# lucky7.net
KiCad netlist of a schematic drawn in EAGLE
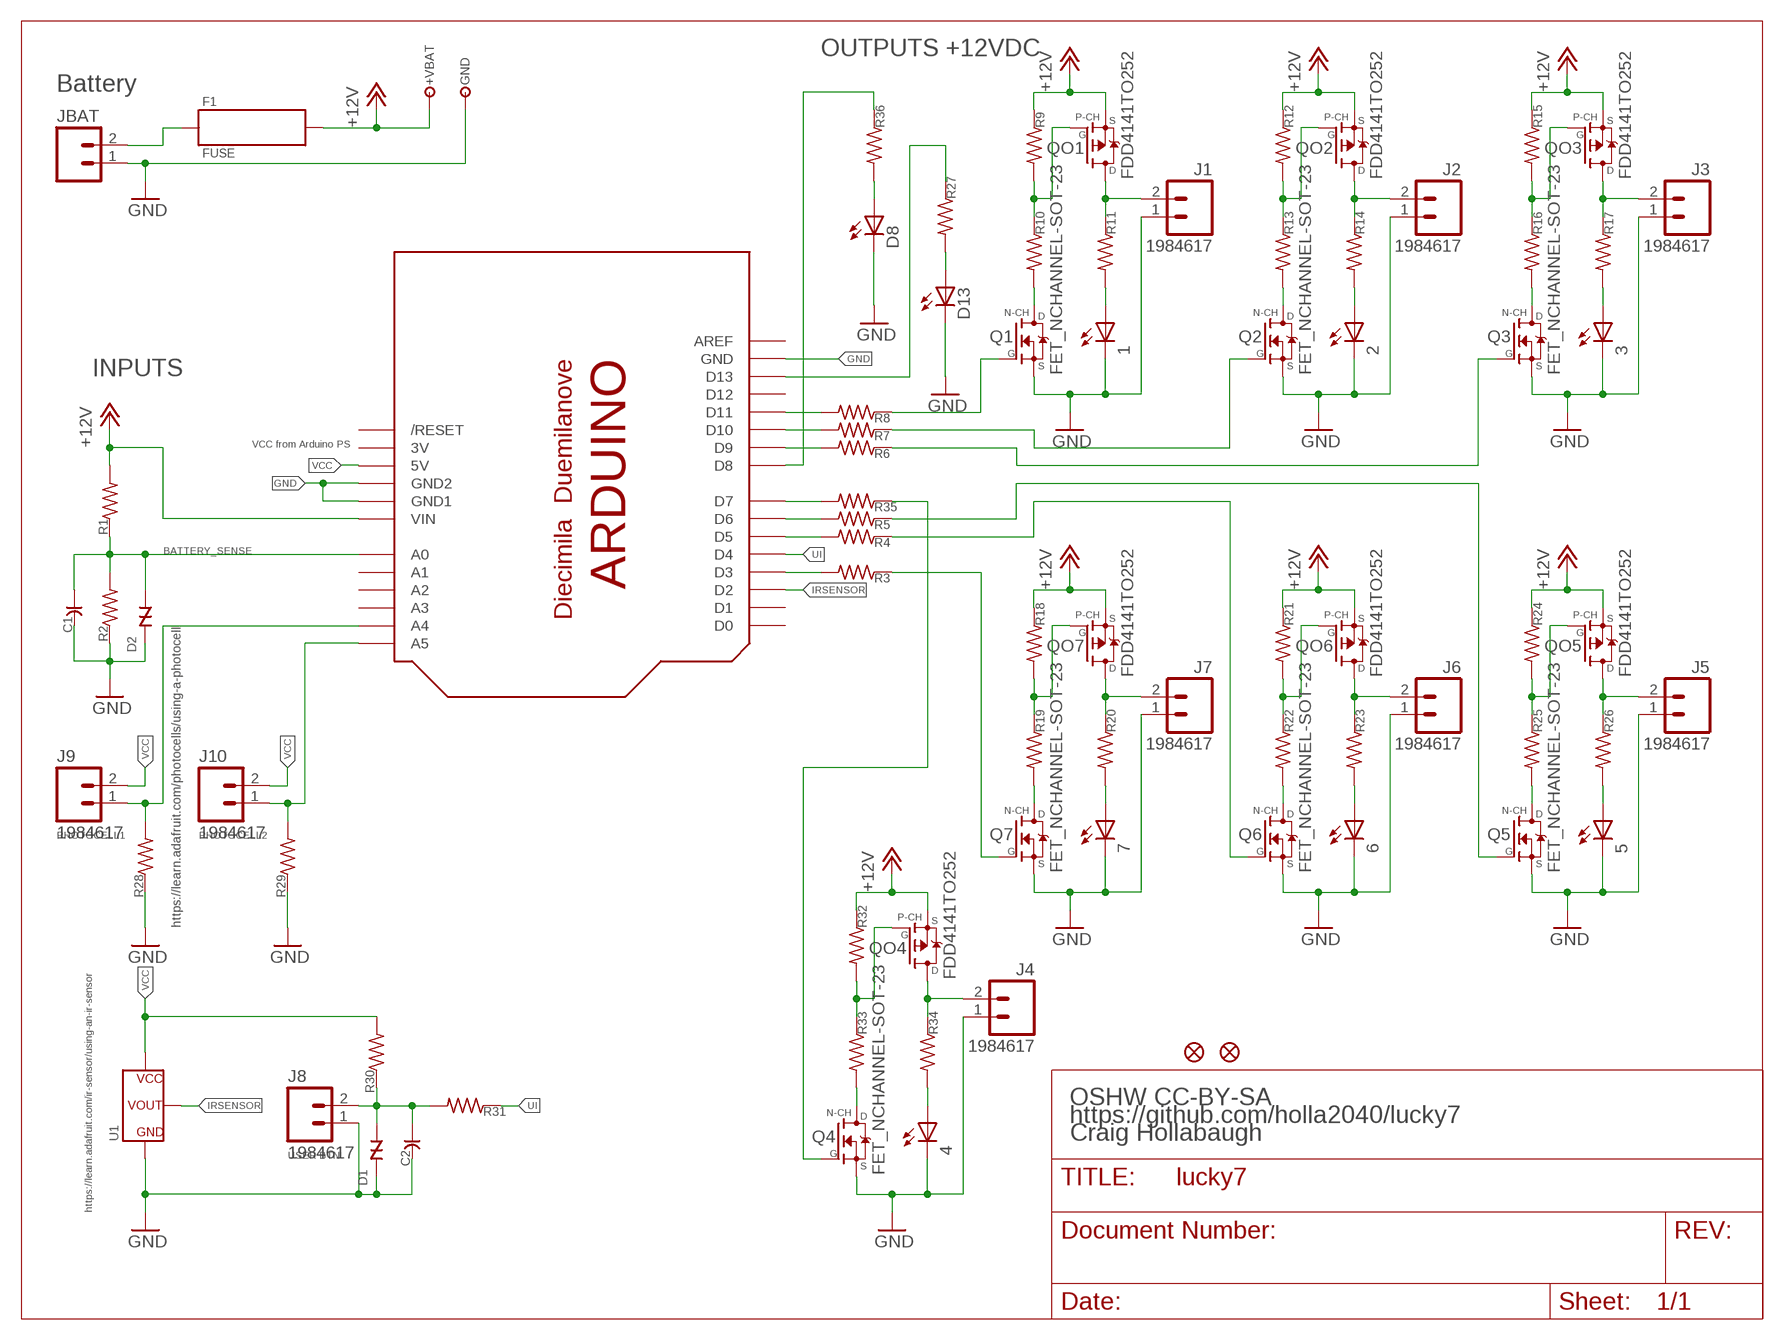
[diagram p0: schematic, sheet 1]

(export (version "E")
  (design (tool "Eeschema 10.0.6"))
  (components
    (comp (ref "+VBAT")
      (value "TESTPOINTTHRU")
      (footprint "eagle-import:TPTHRU")
      (libsource (lib "eagle-import") (part "TESTPOINTTHRU"))
    )
    (comp (ref "1")
      (value "LEDCHIP-LED0805")
      (footprint "eagle-import:CHIP-LED0805")
      (libsource (lib "eagle-import") (part "LEDCHIP-LED0805"))
    )
    (comp (ref "2")
      (value "LEDCHIP-LED0805")
      (footprint "eagle-import:CHIP-LED0805")
      (libsource (lib "eagle-import") (part "LEDCHIP-LED0805"))
    )
    (comp (ref "3")
      (value "LEDCHIP-LED0805")
      (footprint "eagle-import:CHIP-LED0805")
      (libsource (lib "eagle-import") (part "LEDCHIP-LED0805"))
    )
    (comp (ref "4")
      (value "LEDCHIP-LED0805")
      (footprint "eagle-import:CHIP-LED0805")
      (libsource (lib "eagle-import") (part "LEDCHIP-LED0805"))
    )
    (comp (ref "5")
      (value "LEDCHIP-LED0805")
      (footprint "eagle-import:CHIP-LED0805")
      (libsource (lib "eagle-import") (part "LEDCHIP-LED0805"))
    )
    (comp (ref "6")
      (value "LEDCHIP-LED0805")
      (footprint "eagle-import:CHIP-LED0805")
      (libsource (lib "eagle-import") (part "LEDCHIP-LED0805"))
    )
    (comp (ref "7")
      (value "LEDCHIP-LED0805")
      (footprint "eagle-import:CHIP-LED0805")
      (libsource (lib "eagle-import") (part "LEDCHIP-LED0805"))
    )
    (comp (ref "C1")
      (value "C-USC0603")
      (footprint "eagle-import:C0603")
      (libsource (lib "eagle-import") (part "C-USC0603"))
    )
    (comp (ref "C2")
      (value "C-USC0603")
      (footprint "eagle-import:C0603")
      (libsource (lib "eagle-import") (part "C-USC0603"))
    )
    (comp (ref "D1")
      (value "TVS0603")
      (footprint "eagle-import:TVS-0603")
      (libsource (lib "eagle-import") (part "TVS0603"))
    )
    (comp (ref "D2")
      (value "TVS0603")
      (footprint "eagle-import:TVS-0603")
      (libsource (lib "eagle-import") (part "TVS0603"))
    )
    (comp (ref "D8")
      (value "LEDCHIP-LED0805")
      (footprint "eagle-import:CHIP-LED0805")
      (libsource (lib "eagle-import") (part "LEDCHIP-LED0805"))
    )
    (comp (ref "D13")
      (value "LEDCHIP-LED0805")
      (footprint "eagle-import:CHIP-LED0805")
      (libsource (lib "eagle-import") (part "LEDCHIP-LED0805"))
    )
    (comp (ref "F1")
      (value "FUSE")
      (footprint "eagle-import:FUSE-3557-2")
      (libsource (lib "eagle-import") (part "FUSE"))
    )
    (comp (ref "GND")
      (value "TESTPOINTTHRU")
      (footprint "eagle-import:TPTHRU")
      (libsource (lib "eagle-import") (part "TESTPOINTTHRU"))
    )
    (comp (ref "J1")
      (value "1984617")
      (footprint "eagle-import:1984617")
      (libsource (lib "eagle-import") (part "1984617"))
    )
    (comp (ref "J2")
      (value "1984617")
      (footprint "eagle-import:1984617")
      (libsource (lib "eagle-import") (part "1984617"))
    )
    (comp (ref "J3")
      (value "1984617")
      (footprint "eagle-import:1984617")
      (libsource (lib "eagle-import") (part "1984617"))
    )
    (comp (ref "J4")
      (value "1984617")
      (footprint "eagle-import:1984617")
      (libsource (lib "eagle-import") (part "1984617"))
    )
    (comp (ref "J5")
      (value "1984617")
      (footprint "eagle-import:1984617")
      (libsource (lib "eagle-import") (part "1984617"))
    )
    (comp (ref "J6")
      (value "1984617")
      (footprint "eagle-import:1984617")
      (libsource (lib "eagle-import") (part "1984617"))
    )
    (comp (ref "J7")
      (value "1984617")
      (footprint "eagle-import:1984617")
      (libsource (lib "eagle-import") (part "1984617"))
    )
    (comp (ref "J8")
      (value "1984617")
      (footprint "eagle-import:1984617")
      (libsource (lib "eagle-import") (part "1984617"))
    )
    (comp (ref "J9")
      (value "1984617")
      (footprint "eagle-import:1984617")
      (libsource (lib "eagle-import") (part "1984617"))
    )
    (comp (ref "J10")
      (value "1984617")
      (footprint "eagle-import:1984617")
      (libsource (lib "eagle-import") (part "1984617"))
    )
    (comp (ref "JBAT")
      (value "M02-6.35MM")
      (footprint "eagle-import:OSTT702")
      (libsource (lib "eagle-import") (part "M02-6.35MM"))
    )
    (comp (ref "JP1")
      (value "FIDUCIAL1X2")
      (footprint "eagle-import:FIDUCIAL-1X2")
      (libsource (lib "eagle-import") (part "FIDUCIAL1X2"))
    )
    (comp (ref "JP2")
      (value "FIDUCIAL1X2")
      (footprint "eagle-import:FIDUCIAL-1X2")
      (libsource (lib "eagle-import") (part "FIDUCIAL1X2"))
    )
    (comp (ref "Q1")
      (value "FET_NCHANNEL-SOT-23")
      (footprint "eagle-import:SOT-23")
      (libsource (lib "eagle-import") (part "FET_NCHANNEL-SOT-23"))
    )
    (comp (ref "Q2")
      (value "FET_NCHANNEL-SOT-23")
      (footprint "eagle-import:SOT-23")
      (libsource (lib "eagle-import") (part "FET_NCHANNEL-SOT-23"))
    )
    (comp (ref "Q3")
      (value "FET_NCHANNEL-SOT-23")
      (footprint "eagle-import:SOT-23")
      (libsource (lib "eagle-import") (part "FET_NCHANNEL-SOT-23"))
    )
    (comp (ref "Q4")
      (value "FET_NCHANNEL-SOT-23")
      (footprint "eagle-import:SOT-23")
      (libsource (lib "eagle-import") (part "FET_NCHANNEL-SOT-23"))
    )
    (comp (ref "Q5")
      (value "FET_NCHANNEL-SOT-23")
      (footprint "eagle-import:SOT-23")
      (libsource (lib "eagle-import") (part "FET_NCHANNEL-SOT-23"))
    )
    (comp (ref "Q6")
      (value "FET_NCHANNEL-SOT-23")
      (footprint "eagle-import:SOT-23")
      (libsource (lib "eagle-import") (part "FET_NCHANNEL-SOT-23"))
    )
    (comp (ref "Q7")
      (value "FET_NCHANNEL-SOT-23")
      (footprint "eagle-import:SOT-23")
      (libsource (lib "eagle-import") (part "FET_NCHANNEL-SOT-23"))
    )
    (comp (ref "QO1")
      (value "FDD4141TO252")
      (footprint "eagle-import:TO252")
      (libsource (lib "eagle-import") (part "FDD4141TO252"))
    )
    (comp (ref "QO2")
      (value "FDD4141TO252")
      (footprint "eagle-import:TO252")
      (libsource (lib "eagle-import") (part "FDD4141TO252"))
    )
    (comp (ref "QO3")
      (value "FDD4141TO252")
      (footprint "eagle-import:TO252")
      (libsource (lib "eagle-import") (part "FDD4141TO252"))
    )
    (comp (ref "QO4")
      (value "FDD4141TO252")
      (footprint "eagle-import:TO252")
      (libsource (lib "eagle-import") (part "FDD4141TO252"))
    )
    (comp (ref "QO5")
      (value "FDD4141TO252")
      (footprint "eagle-import:TO252")
      (libsource (lib "eagle-import") (part "FDD4141TO252"))
    )
    (comp (ref "QO6")
      (value "FDD4141TO252")
      (footprint "eagle-import:TO252")
      (libsource (lib "eagle-import") (part "FDD4141TO252"))
    )
    (comp (ref "QO7")
      (value "FDD4141TO252")
      (footprint "eagle-import:TO252")
      (libsource (lib "eagle-import") (part "FDD4141TO252"))
    )
    (comp (ref "R1")
      (value "R-US_R0603")
      (footprint "eagle-import:R0603")
      (libsource (lib "eagle-import") (part "R-US_R0603"))
    )
    (comp (ref "R2")
      (value "R-US_R0603")
      (footprint "eagle-import:R0603")
      (libsource (lib "eagle-import") (part "R-US_R0603"))
    )
    (comp (ref "R3")
      (value "R-US_R0603")
      (footprint "eagle-import:R0603")
      (libsource (lib "eagle-import") (part "R-US_R0603"))
    )
    (comp (ref "R4")
      (value "R-US_R0603")
      (footprint "eagle-import:R0603")
      (libsource (lib "eagle-import") (part "R-US_R0603"))
    )
    (comp (ref "R5")
      (value "R-US_R0603")
      (footprint "eagle-import:R0603")
      (libsource (lib "eagle-import") (part "R-US_R0603"))
    )
    (comp (ref "R6")
      (value "R-US_R0603")
      (footprint "eagle-import:R0603")
      (libsource (lib "eagle-import") (part "R-US_R0603"))
    )
    (comp (ref "R7")
      (value "R-US_R0603")
      (footprint "eagle-import:R0603")
      (libsource (lib "eagle-import") (part "R-US_R0603"))
    )
    (comp (ref "R8")
      (value "R-US_R0603")
      (footprint "eagle-import:R0603")
      (libsource (lib "eagle-import") (part "R-US_R0603"))
    )
    (comp (ref "R9")
      (value "R-US_R0603")
      (footprint "eagle-import:R0603")
      (libsource (lib "eagle-import") (part "R-US_R0603"))
    )
    (comp (ref "R10")
      (value "R-US_R0603")
      (footprint "eagle-import:R0603")
      (libsource (lib "eagle-import") (part "R-US_R0603"))
    )
    (comp (ref "R11")
      (value "R-US_R0603")
      (footprint "eagle-import:R0603")
      (libsource (lib "eagle-import") (part "R-US_R0603"))
    )
    (comp (ref "R12")
      (value "R-US_R0603")
      (footprint "eagle-import:R0603")
      (libsource (lib "eagle-import") (part "R-US_R0603"))
    )
    (comp (ref "R13")
      (value "R-US_R0603")
      (footprint "eagle-import:R0603")
      (libsource (lib "eagle-import") (part "R-US_R0603"))
    )
    (comp (ref "R14")
      (value "R-US_R0603")
      (footprint "eagle-import:R0603")
      (libsource (lib "eagle-import") (part "R-US_R0603"))
    )
    (comp (ref "R15")
      (value "R-US_R0603")
      (footprint "eagle-import:R0603")
      (libsource (lib "eagle-import") (part "R-US_R0603"))
    )
    (comp (ref "R16")
      (value "R-US_R0603")
      (footprint "eagle-import:R0603")
      (libsource (lib "eagle-import") (part "R-US_R0603"))
    )
    (comp (ref "R17")
      (value "R-US_R0603")
      (footprint "eagle-import:R0603")
      (libsource (lib "eagle-import") (part "R-US_R0603"))
    )
    (comp (ref "R18")
      (value "R-US_R0603")
      (footprint "eagle-import:R0603")
      (libsource (lib "eagle-import") (part "R-US_R0603"))
    )
    (comp (ref "R19")
      (value "R-US_R0603")
      (footprint "eagle-import:R0603")
      (libsource (lib "eagle-import") (part "R-US_R0603"))
    )
    (comp (ref "R20")
      (value "R-US_R0603")
      (footprint "eagle-import:R0603")
      (libsource (lib "eagle-import") (part "R-US_R0603"))
    )
    (comp (ref "R21")
      (value "R-US_R0603")
      (footprint "eagle-import:R0603")
      (libsource (lib "eagle-import") (part "R-US_R0603"))
    )
    (comp (ref "R22")
      (value "R-US_R0603")
      (footprint "eagle-import:R0603")
      (libsource (lib "eagle-import") (part "R-US_R0603"))
    )
    (comp (ref "R23")
      (value "R-US_R0603")
      (footprint "eagle-import:R0603")
      (libsource (lib "eagle-import") (part "R-US_R0603"))
    )
    (comp (ref "R24")
      (value "R-US_R0603")
      (footprint "eagle-import:R0603")
      (libsource (lib "eagle-import") (part "R-US_R0603"))
    )
    (comp (ref "R25")
      (value "R-US_R0603")
      (footprint "eagle-import:R0603")
      (libsource (lib "eagle-import") (part "R-US_R0603"))
    )
    (comp (ref "R26")
      (value "R-US_R0603")
      (footprint "eagle-import:R0603")
      (libsource (lib "eagle-import") (part "R-US_R0603"))
    )
    (comp (ref "R27")
      (value "R-US_R0603")
      (footprint "eagle-import:R0603")
      (libsource (lib "eagle-import") (part "R-US_R0603"))
    )
    (comp (ref "R28")
      (value "R-US_R0603")
      (footprint "eagle-import:R0603")
      (libsource (lib "eagle-import") (part "R-US_R0603"))
    )
    (comp (ref "R29")
      (value "R-US_R0603")
      (footprint "eagle-import:R0603")
      (libsource (lib "eagle-import") (part "R-US_R0603"))
    )
    (comp (ref "R30")
      (value "R-US_R0603")
      (footprint "eagle-import:R0603")
      (libsource (lib "eagle-import") (part "R-US_R0603"))
    )
    (comp (ref "R31")
      (value "R-US_R0603")
      (footprint "eagle-import:R0603")
      (libsource (lib "eagle-import") (part "R-US_R0603"))
    )
    (comp (ref "R32")
      (value "R-US_R0603")
      (footprint "eagle-import:R0603")
      (libsource (lib "eagle-import") (part "R-US_R0603"))
    )
    (comp (ref "R33")
      (value "R-US_R0603")
      (footprint "eagle-import:R0603")
      (libsource (lib "eagle-import") (part "R-US_R0603"))
    )
    (comp (ref "R34")
      (value "R-US_R0603")
      (footprint "eagle-import:R0603")
      (libsource (lib "eagle-import") (part "R-US_R0603"))
    )
    (comp (ref "R35")
      (value "R-US_R0603")
      (footprint "eagle-import:R0603")
      (libsource (lib "eagle-import") (part "R-US_R0603"))
    )
    (comp (ref "R36")
      (value "R-US_R0603")
      (footprint "eagle-import:R0603")
      (libsource (lib "eagle-import") (part "R-US_R0603"))
    )
    (comp (ref "U1")
      (value "IRDETECTOR-THRU")
      (footprint "eagle-import:IRDETECTOR-THRU")
      (libsource (lib "eagle-import") (part "IRDETECTOR-THRU"))
    )
    (comp (ref "U100")
      (value "ARDUINO-BPLACE")
      (footprint "eagle-import:ARDUINO-BPLACE")
      (libsource (lib "eagle-import") (part "ARDUINO-BPLACE"))
    )
  )
  (nets
    (net (code "1") (name "+12V") (class "Default")
      (node (ref "+VBAT") (pin "1") (pinfunction "P$1_1") (pintype "bidirectional"))
      (node (ref "F1") (pin "2@1") (pinfunction "P$2_2@1") (pintype "bidirectional"))
      (node (ref "F1") (pin "2@2") (pinfunction "P$2_2@2") (pintype "bidirectional"))
      (node (ref "QO1") (pin "2") (pinfunction "S_2") (pintype "passive"))
      (node (ref "QO2") (pin "2") (pinfunction "S_2") (pintype "passive"))
      (node (ref "QO3") (pin "2") (pinfunction "S_2") (pintype "passive"))
      (node (ref "QO4") (pin "2") (pinfunction "S_2") (pintype "passive"))
      (node (ref "QO5") (pin "2") (pinfunction "S_2") (pintype "passive"))
      (node (ref "QO6") (pin "2") (pinfunction "S_2") (pintype "passive"))
      (node (ref "QO7") (pin "2") (pinfunction "S_2") (pintype "passive"))
      (node (ref "R1") (pin "2") (pinfunction "2_2") (pintype "passive"))
      (node (ref "R12") (pin "1") (pinfunction "1_1") (pintype "passive"))
      (node (ref "R15") (pin "1") (pinfunction "1_1") (pintype "passive"))
      (node (ref "R18") (pin "1") (pinfunction "1_1") (pintype "passive"))
      (node (ref "R21") (pin "1") (pinfunction "1_1") (pintype "passive"))
      (node (ref "R24") (pin "1") (pinfunction "1_1") (pintype "passive"))
      (node (ref "R32") (pin "1") (pinfunction "1_1") (pintype "passive"))
      (node (ref "R9") (pin "1") (pinfunction "1_1") (pintype "passive"))
      (node (ref "U100") (pin "VIN") (pinfunction "VIN_VIN") (pintype "power_in"))
    )
    (net (code "2") (name "/3V") (class "Default")
      (node (ref "U100") (pin "3V") (pinfunction "3V_3V") (pintype "power_in"))
    )
    (net (code "3") (name "/BATTERY_SENSE") (class "Default")
      (node (ref "C1") (pin "1") (pinfunction "1_1") (pintype "passive"))
      (node (ref "D2") (pin "1") (pinfunction "1_1") (pintype "bidirectional"))
      (node (ref "R1") (pin "1") (pinfunction "1_1") (pintype "passive"))
      (node (ref "R2") (pin "2") (pinfunction "2_2") (pintype "passive"))
      (node (ref "U100") (pin "A0") (pinfunction "A0_A0") (pintype "bidirectional"))
    )
    (net (code "4") (name "GND") (class "Default")
      (node (ref "1") (pin "C") (pinfunction "C_C") (pintype "passive"))
      (node (ref "2") (pin "C") (pinfunction "C_C") (pintype "passive"))
      (node (ref "3") (pin "C") (pinfunction "C_C") (pintype "passive"))
      (node (ref "4") (pin "C") (pinfunction "C_C") (pintype "passive"))
      (node (ref "5") (pin "C") (pinfunction "C_C") (pintype "passive"))
      (node (ref "6") (pin "C") (pinfunction "C_C") (pintype "passive"))
      (node (ref "7") (pin "C") (pinfunction "C_C") (pintype "passive"))
      (node (ref "C1") (pin "2") (pinfunction "2_2") (pintype "passive"))
      (node (ref "C2") (pin "2") (pinfunction "2_2") (pintype "passive"))
      (node (ref "D1") (pin "2") (pinfunction "2_2") (pintype "bidirectional"))
      (node (ref "D13") (pin "C") (pinfunction "C_C") (pintype "passive"))
      (node (ref "D2") (pin "2") (pinfunction "2_2") (pintype "bidirectional"))
      (node (ref "D8") (pin "C") (pinfunction "C_C") (pintype "passive"))
      (node (ref "GND") (pin "1") (pinfunction "P$1_1") (pintype "bidirectional"))
      (node (ref "J1") (pin "1") (pinfunction "1_1") (pintype "passive"))
      (node (ref "J2") (pin "1") (pinfunction "1_1") (pintype "passive"))
      (node (ref "J3") (pin "1") (pinfunction "1_1") (pintype "passive"))
      (node (ref "J4") (pin "1") (pinfunction "1_1") (pintype "passive"))
      (node (ref "J5") (pin "1") (pinfunction "1_1") (pintype "passive"))
      (node (ref "J6") (pin "1") (pinfunction "1_1") (pintype "passive"))
      (node (ref "J7") (pin "1") (pinfunction "1_1") (pintype "passive"))
      (node (ref "J8") (pin "1") (pinfunction "1_1") (pintype "passive"))
      (node (ref "JBAT") (pin "1") (pinfunction "1_1") (pintype "passive"))
      (node (ref "Q1") (pin "3") (pinfunction "S_3") (pintype "passive"))
      (node (ref "Q2") (pin "3") (pinfunction "S_3") (pintype "passive"))
      (node (ref "Q3") (pin "3") (pinfunction "S_3") (pintype "passive"))
      (node (ref "Q4") (pin "3") (pinfunction "S_3") (pintype "passive"))
      (node (ref "Q5") (pin "3") (pinfunction "S_3") (pintype "passive"))
      (node (ref "Q6") (pin "3") (pinfunction "S_3") (pintype "passive"))
      (node (ref "Q7") (pin "3") (pinfunction "S_3") (pintype "passive"))
      (node (ref "R2") (pin "1") (pinfunction "1_1") (pintype "passive"))
      (node (ref "R28") (pin "1") (pinfunction "1_1") (pintype "passive"))
      (node (ref "R29") (pin "1") (pinfunction "1_1") (pintype "passive"))
      (node (ref "U1") (pin "GND") (pinfunction "GND_GND") (pintype "bidirectional"))
      (node (ref "U100") (pin "GND") (pinfunction "GND_GND") (pintype "power_in"))
      (node (ref "U100") (pin "GND1") (pinfunction "GND1_GND1") (pintype "power_in"))
      (node (ref "U100") (pin "GND2") (pinfunction "GND2_GND2") (pintype "power_in"))
    )
    (net (code "5") (name "IRSENSOR") (class "Default")
      (node (ref "U1") (pin "VOUT") (pinfunction "VOUT_VOUT") (pintype "bidirectional"))
      (node (ref "U100") (pin "D2") (pinfunction "D2_D2") (pintype "bidirectional"))
    )
    (net (code "6") (name "Net-(1-PadA)") (class "Default")
      (node (ref "1") (pin "A") (pinfunction "A_A") (pintype "passive"))
      (node (ref "R11") (pin "2") (pinfunction "2_2") (pintype "passive"))
    )
    (net (code "7") (name "Net-(2-PadA)") (class "Default")
      (node (ref "2") (pin "A") (pinfunction "A_A") (pintype "passive"))
      (node (ref "R14") (pin "2") (pinfunction "2_2") (pintype "passive"))
    )
    (net (code "8") (name "Net-(3-PadA)") (class "Default")
      (node (ref "3") (pin "A") (pinfunction "A_A") (pintype "passive"))
      (node (ref "R17") (pin "2") (pinfunction "2_2") (pintype "passive"))
    )
    (net (code "9") (name "Net-(4-PadA)") (class "Default")
      (node (ref "4") (pin "A") (pinfunction "A_A") (pintype "passive"))
      (node (ref "R34") (pin "2") (pinfunction "2_2") (pintype "passive"))
    )
    (net (code "10") (name "Net-(5-PadA)") (class "Default")
      (node (ref "5") (pin "A") (pinfunction "A_A") (pintype "passive"))
      (node (ref "R26") (pin "2") (pinfunction "2_2") (pintype "passive"))
    )
    (net (code "11") (name "Net-(6-PadA)") (class "Default")
      (node (ref "6") (pin "A") (pinfunction "A_A") (pintype "passive"))
      (node (ref "R23") (pin "2") (pinfunction "2_2") (pintype "passive"))
    )
    (net (code "12") (name "Net-(7-PadA)") (class "Default")
      (node (ref "7") (pin "A") (pinfunction "A_A") (pintype "passive"))
      (node (ref "R20") (pin "2") (pinfunction "2_2") (pintype "passive"))
    )
    (net (code "13") (name "Net-(C2-Pad1)") (class "Default")
      (node (ref "C2") (pin "1") (pinfunction "1_1") (pintype "passive"))
      (node (ref "D1") (pin "1") (pinfunction "1_1") (pintype "bidirectional"))
      (node (ref "J8") (pin "2") (pinfunction "2_2") (pintype "passive"))
      (node (ref "R30") (pin "1") (pinfunction "1_1") (pintype "passive"))
      (node (ref "R31") (pin "2") (pinfunction "2_2") (pintype "passive"))
    )
    (net (code "14") (name "Net-(D8-PadA)") (class "Default")
      (node (ref "D8") (pin "A") (pinfunction "A_A") (pintype "passive"))
      (node (ref "R36") (pin "2") (pinfunction "2_2") (pintype "passive"))
    )
    (net (code "15") (name "Net-(D13-PadA)") (class "Default")
      (node (ref "D13") (pin "A") (pinfunction "A_A") (pintype "passive"))
      (node (ref "R27") (pin "2") (pinfunction "2_2") (pintype "passive"))
    )
    (net (code "16") (name "Net-(F1-P$1-Pad1@1)") (class "Default")
      (node (ref "F1") (pin "1@1") (pinfunction "P$1_1@1") (pintype "bidirectional"))
      (node (ref "F1") (pin "1@2") (pinfunction "P$1_1@2") (pintype "bidirectional"))
      (node (ref "JBAT") (pin "2") (pinfunction "2_2") (pintype "passive"))
    )
    (net (code "17") (name "Net-(J9-Pad1)") (class "Default")
      (node (ref "J9") (pin "1") (pinfunction "1_1") (pintype "passive"))
      (node (ref "R28") (pin "2") (pinfunction "2_2") (pintype "passive"))
      (node (ref "U100") (pin "A4") (pinfunction "A4_A4") (pintype "bidirectional"))
    )
    (net (code "18") (name "Net-(J10-Pad1)") (class "Default")
      (node (ref "J10") (pin "1") (pinfunction "1_1") (pintype "passive"))
      (node (ref "R29") (pin "2") (pinfunction "2_2") (pintype "passive"))
      (node (ref "U100") (pin "A5") (pinfunction "A5_A5") (pintype "bidirectional"))
    )
    (net (code "19") (name "Net-(Q1-D)") (class "Default")
      (node (ref "Q1") (pin "1") (pinfunction "D_1") (pintype "passive"))
      (node (ref "R10") (pin "2") (pinfunction "2_2") (pintype "passive"))
    )
    (net (code "20") (name "Net-(Q1-G)") (class "Default")
      (node (ref "Q1") (pin "2") (pinfunction "G_2") (pintype "passive"))
      (node (ref "R8") (pin "1") (pinfunction "1_1") (pintype "passive"))
    )
    (net (code "21") (name "Net-(Q2-D)") (class "Default")
      (node (ref "Q2") (pin "1") (pinfunction "D_1") (pintype "passive"))
      (node (ref "R13") (pin "2") (pinfunction "2_2") (pintype "passive"))
    )
    (net (code "22") (name "Net-(Q2-G)") (class "Default")
      (node (ref "Q2") (pin "2") (pinfunction "G_2") (pintype "passive"))
      (node (ref "R7") (pin "1") (pinfunction "1_1") (pintype "passive"))
    )
    (net (code "23") (name "Net-(Q3-D)") (class "Default")
      (node (ref "Q3") (pin "1") (pinfunction "D_1") (pintype "passive"))
      (node (ref "R16") (pin "2") (pinfunction "2_2") (pintype "passive"))
    )
    (net (code "24") (name "Net-(Q3-G)") (class "Default")
      (node (ref "Q3") (pin "2") (pinfunction "G_2") (pintype "passive"))
      (node (ref "R6") (pin "1") (pinfunction "1_1") (pintype "passive"))
    )
    (net (code "25") (name "Net-(Q4-D)") (class "Default")
      (node (ref "Q4") (pin "1") (pinfunction "D_1") (pintype "passive"))
      (node (ref "R33") (pin "2") (pinfunction "2_2") (pintype "passive"))
    )
    (net (code "26") (name "Net-(Q4-G)") (class "Default")
      (node (ref "Q4") (pin "2") (pinfunction "G_2") (pintype "passive"))
      (node (ref "R35") (pin "1") (pinfunction "1_1") (pintype "passive"))
    )
    (net (code "27") (name "Net-(Q5-D)") (class "Default")
      (node (ref "Q5") (pin "1") (pinfunction "D_1") (pintype "passive"))
      (node (ref "R25") (pin "2") (pinfunction "2_2") (pintype "passive"))
    )
    (net (code "28") (name "Net-(Q5-G)") (class "Default")
      (node (ref "Q5") (pin "2") (pinfunction "G_2") (pintype "passive"))
      (node (ref "R5") (pin "1") (pinfunction "1_1") (pintype "passive"))
    )
    (net (code "29") (name "Net-(Q6-D)") (class "Default")
      (node (ref "Q6") (pin "1") (pinfunction "D_1") (pintype "passive"))
      (node (ref "R22") (pin "2") (pinfunction "2_2") (pintype "passive"))
    )
    (net (code "30") (name "Net-(Q6-G)") (class "Default")
      (node (ref "Q6") (pin "2") (pinfunction "G_2") (pintype "passive"))
      (node (ref "R4") (pin "1") (pinfunction "1_1") (pintype "passive"))
    )
    (net (code "31") (name "Net-(Q7-D)") (class "Default")
      (node (ref "Q7") (pin "1") (pinfunction "D_1") (pintype "passive"))
      (node (ref "R19") (pin "2") (pinfunction "2_2") (pintype "passive"))
    )
    (net (code "32") (name "Net-(Q7-G)") (class "Default")
      (node (ref "Q7") (pin "2") (pinfunction "G_2") (pintype "passive"))
      (node (ref "R3") (pin "1") (pinfunction "1_1") (pintype "passive"))
    )
    (net (code "33") (name "Net-(QO1-D)") (class "Default")
      (node (ref "J1") (pin "2") (pinfunction "2_2") (pintype "passive"))
      (node (ref "QO1") (pin "3") (pinfunction "D_3") (pintype "passive"))
      (node (ref "R11") (pin "1") (pinfunction "1_1") (pintype "passive"))
    )
    (net (code "34") (name "Net-(QO1-G)") (class "Default")
      (node (ref "QO1") (pin "1") (pinfunction "G_1") (pintype "passive"))
      (node (ref "R10") (pin "1") (pinfunction "1_1") (pintype "passive"))
      (node (ref "R9") (pin "2") (pinfunction "2_2") (pintype "passive"))
    )
    (net (code "35") (name "Net-(QO2-D)") (class "Default")
      (node (ref "J2") (pin "2") (pinfunction "2_2") (pintype "passive"))
      (node (ref "QO2") (pin "3") (pinfunction "D_3") (pintype "passive"))
      (node (ref "R14") (pin "1") (pinfunction "1_1") (pintype "passive"))
    )
    (net (code "36") (name "Net-(QO2-G)") (class "Default")
      (node (ref "QO2") (pin "1") (pinfunction "G_1") (pintype "passive"))
      (node (ref "R12") (pin "2") (pinfunction "2_2") (pintype "passive"))
      (node (ref "R13") (pin "1") (pinfunction "1_1") (pintype "passive"))
    )
    (net (code "37") (name "Net-(QO3-D)") (class "Default")
      (node (ref "J3") (pin "2") (pinfunction "2_2") (pintype "passive"))
      (node (ref "QO3") (pin "3") (pinfunction "D_3") (pintype "passive"))
      (node (ref "R17") (pin "1") (pinfunction "1_1") (pintype "passive"))
    )
    (net (code "38") (name "Net-(QO3-G)") (class "Default")
      (node (ref "QO3") (pin "1") (pinfunction "G_1") (pintype "passive"))
      (node (ref "R15") (pin "2") (pinfunction "2_2") (pintype "passive"))
      (node (ref "R16") (pin "1") (pinfunction "1_1") (pintype "passive"))
    )
    (net (code "39") (name "Net-(QO4-D)") (class "Default")
      (node (ref "J4") (pin "2") (pinfunction "2_2") (pintype "passive"))
      (node (ref "QO4") (pin "3") (pinfunction "D_3") (pintype "passive"))
      (node (ref "R34") (pin "1") (pinfunction "1_1") (pintype "passive"))
    )
    (net (code "40") (name "Net-(QO4-G)") (class "Default")
      (node (ref "QO4") (pin "1") (pinfunction "G_1") (pintype "passive"))
      (node (ref "R32") (pin "2") (pinfunction "2_2") (pintype "passive"))
      (node (ref "R33") (pin "1") (pinfunction "1_1") (pintype "passive"))
    )
    (net (code "41") (name "Net-(QO5-D)") (class "Default")
      (node (ref "J5") (pin "2") (pinfunction "2_2") (pintype "passive"))
      (node (ref "QO5") (pin "3") (pinfunction "D_3") (pintype "passive"))
      (node (ref "R26") (pin "1") (pinfunction "1_1") (pintype "passive"))
    )
    (net (code "42") (name "Net-(QO5-G)") (class "Default")
      (node (ref "QO5") (pin "1") (pinfunction "G_1") (pintype "passive"))
      (node (ref "R24") (pin "2") (pinfunction "2_2") (pintype "passive"))
      (node (ref "R25") (pin "1") (pinfunction "1_1") (pintype "passive"))
    )
    (net (code "43") (name "Net-(QO6-D)") (class "Default")
      (node (ref "J6") (pin "2") (pinfunction "2_2") (pintype "passive"))
      (node (ref "QO6") (pin "3") (pinfunction "D_3") (pintype "passive"))
      (node (ref "R23") (pin "1") (pinfunction "1_1") (pintype "passive"))
    )
    (net (code "44") (name "Net-(QO6-G)") (class "Default")
      (node (ref "QO6") (pin "1") (pinfunction "G_1") (pintype "passive"))
      (node (ref "R21") (pin "2") (pinfunction "2_2") (pintype "passive"))
      (node (ref "R22") (pin "1") (pinfunction "1_1") (pintype "passive"))
    )
    (net (code "45") (name "Net-(QO7-D)") (class "Default")
      (node (ref "J7") (pin "2") (pinfunction "2_2") (pintype "passive"))
      (node (ref "QO7") (pin "3") (pinfunction "D_3") (pintype "passive"))
      (node (ref "R20") (pin "1") (pinfunction "1_1") (pintype "passive"))
    )
    (net (code "46") (name "Net-(QO7-G)") (class "Default")
      (node (ref "QO7") (pin "1") (pinfunction "G_1") (pintype "passive"))
      (node (ref "R18") (pin "2") (pinfunction "2_2") (pintype "passive"))
      (node (ref "R19") (pin "1") (pinfunction "1_1") (pintype "passive"))
    )
    (net (code "47") (name "Net-(R3-Pad2)") (class "Default")
      (node (ref "R3") (pin "2") (pinfunction "2_2") (pintype "passive"))
      (node (ref "U100") (pin "D3") (pinfunction "D3_D3") (pintype "bidirectional"))
    )
    (net (code "48") (name "Net-(R4-Pad2)") (class "Default")
      (node (ref "R4") (pin "2") (pinfunction "2_2") (pintype "passive"))
      (node (ref "U100") (pin "D5") (pinfunction "D5_D5") (pintype "bidirectional"))
    )
    (net (code "49") (name "Net-(R5-Pad2)") (class "Default")
      (node (ref "R5") (pin "2") (pinfunction "2_2") (pintype "passive"))
      (node (ref "U100") (pin "D6") (pinfunction "D6_D6") (pintype "bidirectional"))
    )
    (net (code "50") (name "Net-(R6-Pad2)") (class "Default")
      (node (ref "R6") (pin "2") (pinfunction "2_2") (pintype "passive"))
      (node (ref "U100") (pin "D9") (pinfunction "D9_D9") (pintype "bidirectional"))
    )
    (net (code "51") (name "Net-(R7-Pad2)") (class "Default")
      (node (ref "R7") (pin "2") (pinfunction "2_2") (pintype "passive"))
      (node (ref "U100") (pin "D10") (pinfunction "D10_D10") (pintype "bidirectional"))
    )
    (net (code "52") (name "Net-(R8-Pad2)") (class "Default")
      (node (ref "R8") (pin "2") (pinfunction "2_2") (pintype "passive"))
      (node (ref "U100") (pin "D11") (pinfunction "D11_D11") (pintype "bidirectional"))
    )
    (net (code "53") (name "Net-(R27-Pad1)") (class "Default")
      (node (ref "R27") (pin "1") (pinfunction "1_1") (pintype "passive"))
      (node (ref "U100") (pin "D13") (pinfunction "D13_D13") (pintype "bidirectional"))
    )
    (net (code "54") (name "Net-(R35-Pad2)") (class "Default")
      (node (ref "R35") (pin "2") (pinfunction "2_2") (pintype "passive"))
      (node (ref "U100") (pin "D7") (pinfunction "D7_D7") (pintype "bidirectional"))
    )
    (net (code "55") (name "Net-(R36-Pad1)") (class "Default")
      (node (ref "R36") (pin "1") (pinfunction "1_1") (pintype "passive"))
      (node (ref "U100") (pin "D8") (pinfunction "D8_D8") (pintype "bidirectional"))
    )
    (net (code "56") (name "UI") (class "Default")
      (node (ref "R31") (pin "1") (pinfunction "1_1") (pintype "passive"))
      (node (ref "U100") (pin "D4") (pinfunction "D4_D4") (pintype "bidirectional"))
    )
    (net (code "57") (name "VCC") (class "Default")
      (node (ref "J10") (pin "2") (pinfunction "2_2") (pintype "passive"))
      (node (ref "J9") (pin "2") (pinfunction "2_2") (pintype "passive"))
      (node (ref "R30") (pin "2") (pinfunction "2_2") (pintype "passive"))
      (node (ref "U1") (pin "VCC") (pinfunction "VCC_VCC") (pintype "bidirectional"))
      (node (ref "U100") (pin "5V") (pinfunction "5V_5V") (pintype "power_in"))
    )
    (net (code "58") (name "unconnected-(U100-PadA1)") (class "Default")
      (node (ref "U100") (pin "A1") (pinfunction "A1_A1") (pintype "bidirectional"))
    )
    (net (code "59") (name "unconnected-(U100-PadA2)") (class "Default")
      (node (ref "U100") (pin "A2") (pinfunction "A2_A2") (pintype "bidirectional"))
    )
    (net (code "60") (name "unconnected-(U100-PadA3)") (class "Default")
      (node (ref "U100") (pin "A3") (pinfunction "A3_A3") (pintype "bidirectional"))
    )
    (net (code "61") (name "unconnected-(U100-PadAREF)") (class "Default")
      (node (ref "U100") (pin "AREF") (pinfunction "AREF_AREF") (pintype "bidirectional"))
    )
    (net (code "62") (name "unconnected-(U100-PadD0)") (class "Default")
      (node (ref "U100") (pin "D0") (pinfunction "D0_D0") (pintype "bidirectional"))
    )
    (net (code "63") (name "unconnected-(U100-PadD1)") (class "Default")
      (node (ref "U100") (pin "D1") (pinfunction "D1_D1") (pintype "bidirectional"))
    )
    (net (code "64") (name "unconnected-(U100-PadD12)") (class "Default")
      (node (ref "U100") (pin "D12") (pinfunction "D12_D12") (pintype "bidirectional"))
    )
    (net (code "65") (name "unconnected-(U100-{slash}RESET-PadRESET)") (class "Default")
      (node (ref "U100") (pin "RESET") (pinfunction "/RESET_RESET") (pintype "bidirectional"))
    )
  )
)
